# 467444_130_3_5-A.net
KiCad netlist of a schematic drawn in Altium Designer
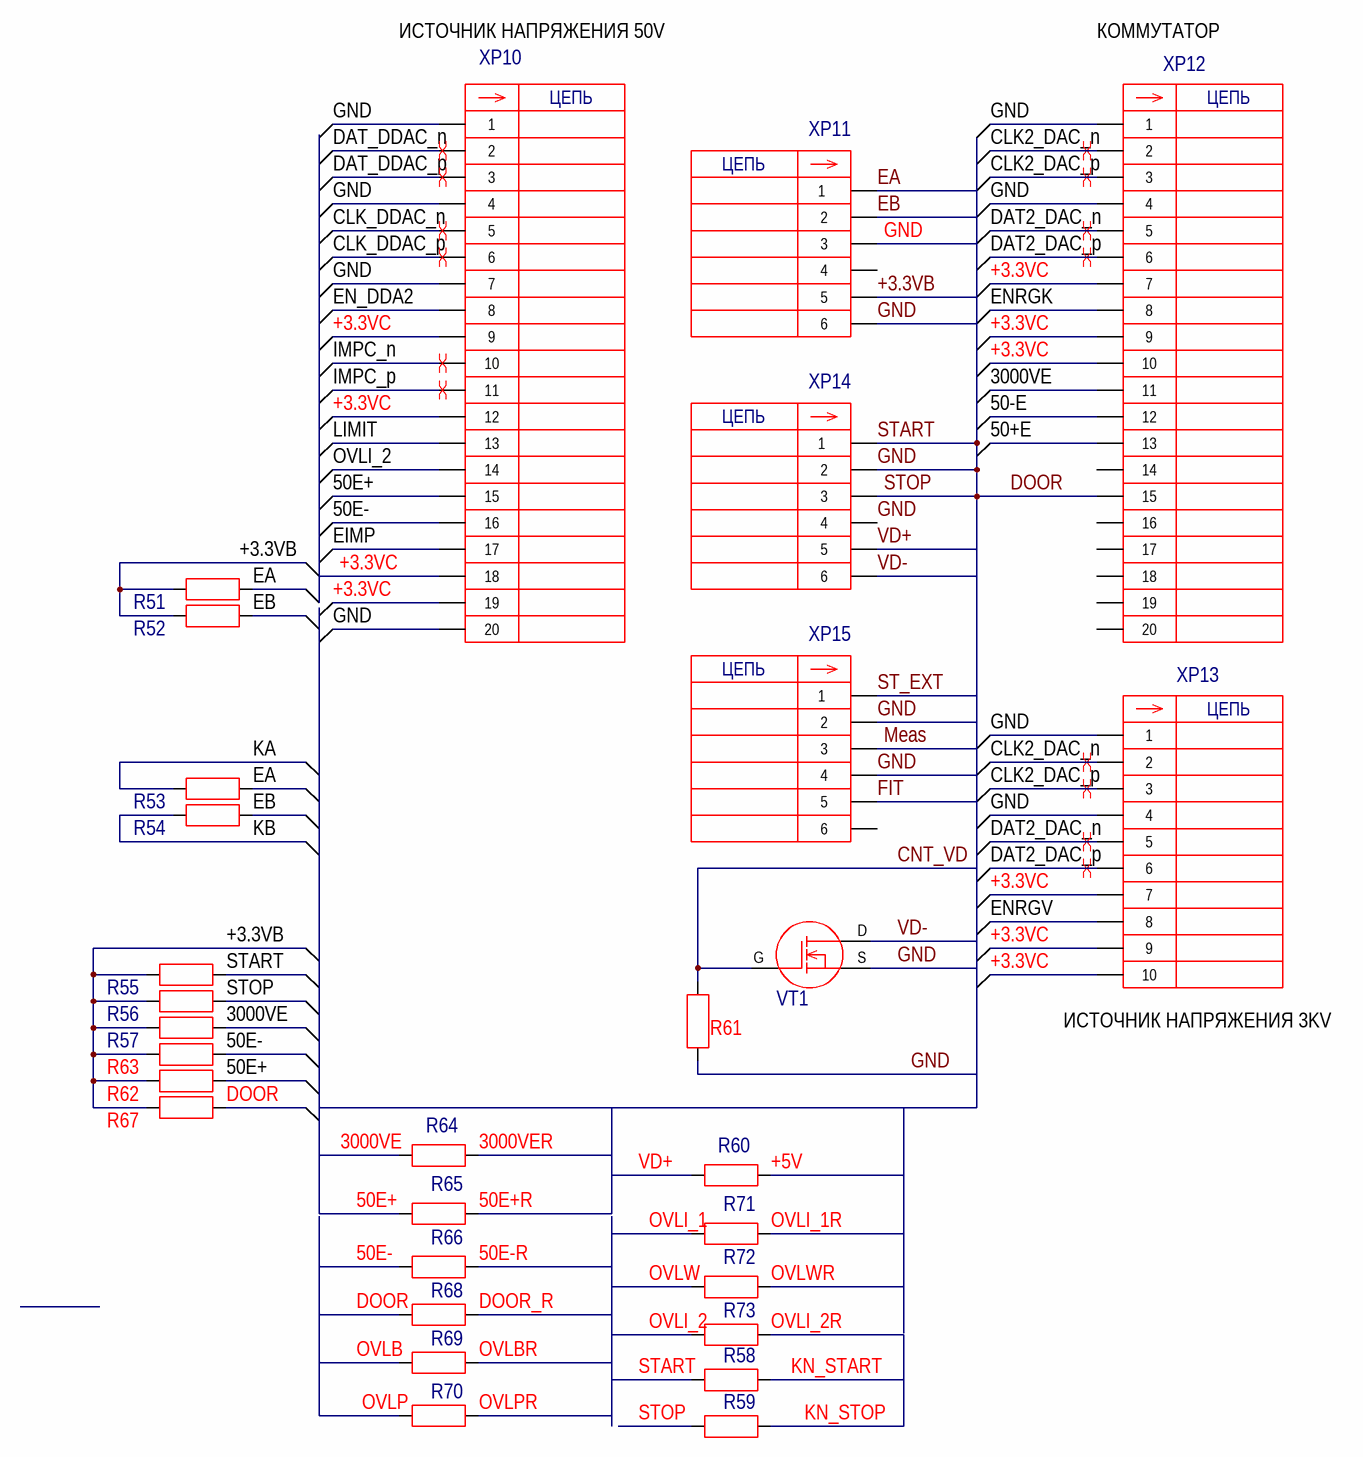
[diagram p0: УШЯИ.467444.130Э3_5-A.SchDoc]

(export (version "E")
  (design (tool "Eeschema 10.0.6"))
  (components
    (comp (ref "R51")
      (value "10k")
      (footprint "R_0805 [2012 Metric]")
      (fields (field (name "TOLERANCE") "±1%"))
      (libsource (lib "lib") (part "R_Const"))
    )
    (comp (ref "R52")
      (value "10k")
      (footprint "R_0805 [2012 Metric]")
      (fields (field (name "TOLERANCE") "±1%"))
      (libsource (lib "lib") (part "R_Const"))
    )
    (comp (ref "R53")
      (value "10k")
      (footprint "R_0805 [2012 Metric]")
      (fields (field (name "TOLERANCE") "±1%"))
      (libsource (lib "lib") (part "R_Const"))
    )
    (comp (ref "R54")
      (value "10k")
      (footprint "R_0805 [2012 Metric]")
      (fields (field (name "TOLERANCE") "±1%"))
      (libsource (lib "lib") (part "R_Const"))
    )
    (comp (ref "R55")
      (value "10k")
      (footprint "R_0805 [2012 Metric]")
      (fields (field (name "TOLERANCE") "±1%"))
      (libsource (lib "lib") (part "R_Const"))
    )
    (comp (ref "R56")
      (value "10k")
      (footprint "R_0805 [2012 Metric]")
      (fields (field (name "TOLERANCE") "±1%"))
      (libsource (lib "lib") (part "R_Const"))
    )
    (comp (ref "R57")
      (value "10k")
      (footprint "R_0805 [2012 Metric]")
      (fields (field (name "TOLERANCE") "±1%"))
      (libsource (lib "lib") (part "R_Const"))
    )
    (comp (ref "R58")
      (value "10k")
      (footprint "R_0805 [2012 Metric]")
      (fields (field (name "TOLERANCE") "±1%"))
      (libsource (lib "lib") (part "R_Const"))
    )
    (comp (ref "R59")
      (value "10k")
      (footprint "R_0805 [2012 Metric]")
      (fields (field (name "TOLERANCE") "±1%"))
      (libsource (lib "lib") (part "R_Const"))
    )
    (comp (ref "R60")
      (value "10k")
      (footprint "R_0805 [2012 Metric]")
      (fields (field (name "TOLERANCE") "±1%"))
      (libsource (lib "lib") (part "R_Const"))
    )
    (comp (ref "R61")
      (value "10k")
      (footprint "R_1206 [3216 Metric]")
      (fields (field (name "TOLERANCE") "±5%"))
      (libsource (lib "Lib_MN") (part "R_Const"))
    )
    (comp (ref "R62")
      (value "10k")
      (footprint "R_0805 [2012 Metric]")
      (fields (field (name "TOLERANCE") "±1%"))
      (libsource (lib "lib") (part "R_Const"))
    )
    (comp (ref "R63")
      (value "10k")
      (footprint "R_0805 [2012 Metric]")
      (fields (field (name "TOLERANCE") "±1%"))
      (libsource (lib "lib") (part "R_Const"))
    )
    (comp (ref "R64")
      (value "10k")
      (footprint "R_0805 [2012 Metric]")
      (fields (field (name "TOLERANCE") "±1%"))
      (libsource (lib "lib") (part "R_Const"))
    )
    (comp (ref "R65")
      (value "10k")
      (footprint "R_0805 [2012 Metric]")
      (fields (field (name "TOLERANCE") "±1%"))
      (libsource (lib "lib") (part "R_Const"))
    )
    (comp (ref "R66")
      (value "10k")
      (footprint "R_0805 [2012 Metric]")
      (fields (field (name "TOLERANCE") "±1%"))
      (libsource (lib "lib") (part "R_Const"))
    )
    (comp (ref "R67")
      (value "10k")
      (footprint "R_0805 [2012 Metric]")
      (fields (field (name "TOLERANCE") "±1%"))
      (libsource (lib "lib") (part "R_Const"))
    )
    (comp (ref "R68")
      (value "10k")
      (footprint "R_0805 [2012 Metric]")
      (fields (field (name "TOLERANCE") "±1%"))
      (libsource (lib "lib") (part "R_Const"))
    )
    (comp (ref "R69")
      (value "10k")
      (footprint "R_0805 [2012 Metric]")
      (fields (field (name "TOLERANCE") "±1%"))
      (libsource (lib "lib") (part "R_Const"))
    )
    (comp (ref "R70")
      (value "10k")
      (footprint "R_0805 [2012 Metric]")
      (fields (field (name "TOLERANCE") "±1%"))
      (libsource (lib "lib") (part "R_Const"))
    )
    (comp (ref "R71")
      (value "10k")
      (footprint "R_0805 [2012 Metric]")
      (fields (field (name "TOLERANCE") "±1%"))
      (libsource (lib "lib") (part "R_Const"))
    )
    (comp (ref "R72")
      (value "10k")
      (footprint "R_0805 [2012 Metric]")
      (fields (field (name "TOLERANCE") "±1%"))
      (libsource (lib "lib") (part "R_Const"))
    )
    (comp (ref "R73")
      (value "10k")
      (footprint "R_0805 [2012 Metric]")
      (fields (field (name "TOLERANCE") "±1%"))
      (libsource (lib "lib") (part "R_Const"))
    )
    (comp (ref "VT1")
      (value "NDS7002A")
      (footprint "SOT-23-3_[TO-236AB]_Transistor_n")
      (description "Транзистор n-канальный, изолированный затвор")
      (fields (field (name "MANUFACTURER") "Onsemi"))
      (libsource (lib "Lib_MN") (part "n-channel"))
    )
    (comp (ref "XP10")
      (value "BH2-20R")
      (footprint "BH2-20R")
      (description "Male, 20 pins, 2 rows, Right Angle, DS1014-20RF1B-B, 2 mm")
      (fields (field (name "MANUFACTURER") "Connfly electronic"))
      (libsource (lib "lib") (part "M_20"))
    )
    (comp (ref "XP11")
      (value "AMPMODU II 280372-2")
      (footprint "AMP II-280372-2")
      (description "Male, 6 pin, 1 row, Vertical, Board-to-Board, 2.54 mm")
      (fields (field (name "MANUFACTURER") "TE Connectivity"))
      (libsource (lib "Lib_MN") (part "M_6"))
    )
    (comp (ref "XP12")
      (value "BH2-20R")
      (footprint "BH2-20R")
      (description "Male, 20 pins, 2 rows, Right Angle, DS1014-20RF1B-B, 2 mm")
      (fields (field (name "MANUFACTURER") "Connfly electronic"))
      (libsource (lib "lib") (part "M_20"))
    )
    (comp (ref "XP13")
      (value "BH2-10R")
      (footprint "BH2-10R")
      (description "Male, 10 pins, 2 rows, Vertical, DS1014-10RF1B-B, 2 mm")
      (fields (field (name "MANUFACTURER") "Connfly electronic"))
      (libsource (lib "lib") (part "M_10"))
    )
    (comp (ref "XP14")
      (value "AMPMODU II 280372-2")
      (footprint "AMP II-280372-2")
      (description "Male, 6 pin, 1 row, Vertical, Board-to-Board, 2.54 mm")
      (fields (field (name "MANUFACTURER") "TE Connectivity"))
      (libsource (lib "Lib_MN") (part "M_6"))
    )
    (comp (ref "XP15")
      (value "AMPMODU II 280372-2")
      (footprint "AMP II-280372-2")
      (description "Male, 6 pin, 1 row, Vertical, Board-to-Board, 2.54 mm")
      (fields (field (name "MANUFACTURER") "TE Connectivity"))
      (libsource (lib "Lib_MN") (part "M_6"))
    )
  )
  (nets
    (net (code "1") (name "/+3.3VB") (class "Default")
      (node (ref "R51") (pin "1") (pinfunction "1_1") (pintype "passive"))
      (node (ref "R52") (pin "1") (pinfunction "1_1") (pintype "passive"))
      (node (ref "R55") (pin "1") (pinfunction "1_1") (pintype "passive"))
      (node (ref "R56") (pin "1") (pinfunction "1_1") (pintype "passive"))
      (node (ref "R57") (pin "1") (pinfunction "1_1") (pintype "passive"))
      (node (ref "R62") (pin "1") (pinfunction "1_1") (pintype "passive"))
      (node (ref "R63") (pin "1") (pinfunction "1_1") (pintype "passive"))
      (node (ref "R67") (pin "1") (pinfunction "1_1") (pintype "passive"))
      (node (ref "XP11") (pin "5") (pinfunction "5_5") (pintype "passive"))
    )
    (net (code "2") (name "/+3.3VC") (class "Default")
      (node (ref "XP10") (pin "12") (pinfunction "12_12") (pintype "passive"))
      (node (ref "XP10") (pin "18") (pinfunction "18_18") (pintype "passive"))
      (node (ref "XP10") (pin "19") (pinfunction "19_19") (pintype "passive"))
      (node (ref "XP10") (pin "9") (pinfunction "9_9") (pintype "passive"))
      (node (ref "XP12") (pin "10") (pinfunction "10_10") (pintype "passive"))
      (node (ref "XP12") (pin "7") (pinfunction "7_7") (pintype "passive"))
      (node (ref "XP12") (pin "9") (pinfunction "9_9") (pintype "passive"))
      (node (ref "XP13") (pin "10") (pinfunction "10_10") (pintype "passive"))
      (node (ref "XP13") (pin "7") (pinfunction "7_7") (pintype "passive"))
      (node (ref "XP13") (pin "9") (pinfunction "9_9") (pintype "passive"))
    )
    (net (code "3") (name "/+5V") (class "Default")
      (node (ref "R60") (pin "2") (pinfunction "2_2") (pintype "passive"))
    )
    (net (code "4") (name "/50+E") (class "Default")
      (node (ref "XP12") (pin "13") (pinfunction "13_13") (pintype "passive"))
    )
    (net (code "5") (name "/50-E") (class "Default")
      (node (ref "XP12") (pin "12") (pinfunction "12_12") (pintype "passive"))
    )
    (net (code "6") (name "/50E+") (class "Default")
      (node (ref "R62") (pin "2") (pinfunction "2_2") (pintype "passive"))
      (node (ref "R65") (pin "1") (pinfunction "1_1") (pintype "passive"))
      (node (ref "XP10") (pin "15") (pinfunction "15_15") (pintype "passive"))
    )
    (net (code "7") (name "/50E+R") (class "Default")
      (node (ref "R65") (pin "2") (pinfunction "2_2") (pintype "passive"))
    )
    (net (code "8") (name "/50E-") (class "Default")
      (node (ref "R63") (pin "2") (pinfunction "2_2") (pintype "passive"))
      (node (ref "R66") (pin "1") (pinfunction "1_1") (pintype "passive"))
      (node (ref "XP10") (pin "16") (pinfunction "16_16") (pintype "passive"))
    )
    (net (code "9") (name "/50E-R") (class "Default")
      (node (ref "R66") (pin "2") (pinfunction "2_2") (pintype "passive"))
    )
    (net (code "10") (name "/3000VE") (class "Default")
      (node (ref "R57") (pin "2") (pinfunction "2_2") (pintype "passive"))
      (node (ref "R64") (pin "1") (pinfunction "1_1") (pintype "passive"))
      (node (ref "XP12") (pin "11") (pinfunction "11_11") (pintype "passive"))
    )
    (net (code "11") (name "/3000VER") (class "Default")
      (node (ref "R64") (pin "2") (pinfunction "2_2") (pintype "passive"))
    )
    (net (code "12") (name "/CLK2_DAC_n") (class "Default")
      (node (ref "XP12") (pin "2") (pinfunction "2_2") (pintype "passive"))
      (node (ref "XP13") (pin "2") (pinfunction "2_2") (pintype "passive"))
    )
    (net (code "13") (name "/CLK2_DAC_p") (class "Default")
      (node (ref "XP12") (pin "3") (pinfunction "3_3") (pintype "passive"))
      (node (ref "XP13") (pin "3") (pinfunction "3_3") (pintype "passive"))
    )
    (net (code "14") (name "/CLK_DDAC_n") (class "Default")
      (node (ref "XP10") (pin "5") (pinfunction "5_5") (pintype "passive"))
    )
    (net (code "15") (name "/CLK_DDAC_p") (class "Default")
      (node (ref "XP10") (pin "6") (pinfunction "6_6") (pintype "passive"))
    )
    (net (code "16") (name "/CNT_VD") (class "Default")
      (node (ref "R61") (pin "2") (pinfunction "2_2") (pintype "passive"))
      (node (ref "VT1") (pin "G") (pinfunction "З_G") (pintype "passive"))
    )
    (net (code "17") (name "/DAT2_DAC_n") (class "Default")
      (node (ref "XP12") (pin "5") (pinfunction "5_5") (pintype "passive"))
      (node (ref "XP13") (pin "5") (pinfunction "5_5") (pintype "passive"))
    )
    (net (code "18") (name "/DAT2_DAC_p") (class "Default")
      (node (ref "XP12") (pin "6") (pinfunction "6_6") (pintype "passive"))
      (node (ref "XP13") (pin "6") (pinfunction "6_6") (pintype "passive"))
    )
    (net (code "19") (name "/DAT_DDAC_n") (class "Default")
      (node (ref "XP10") (pin "2") (pinfunction "2_2") (pintype "passive"))
    )
    (net (code "20") (name "/DAT_DDAC_p") (class "Default")
      (node (ref "XP10") (pin "3") (pinfunction "3_3") (pintype "passive"))
    )
    (net (code "21") (name "/DOOR") (class "Default")
      (node (ref "R55") (pin "2") (pinfunction "2_2") (pintype "passive"))
      (node (ref "R56") (pin "2") (pinfunction "2_2") (pintype "passive"))
      (node (ref "R58") (pin "1") (pinfunction "1_1") (pintype "passive"))
      (node (ref "R59") (pin "1") (pinfunction "1_1") (pintype "passive"))
      (node (ref "R61") (pin "1") (pinfunction "1_1") (pintype "passive"))
      (node (ref "R67") (pin "2") (pinfunction "2_2") (pintype "passive"))
      (node (ref "R68") (pin "1") (pinfunction "1_1") (pintype "passive"))
      (node (ref "VT1") (pin "S") (pinfunction "И_S") (pintype "passive"))
      (node (ref "XP10") (pin "1") (pinfunction "1_1") (pintype "passive"))
      (node (ref "XP10") (pin "20") (pinfunction "20_20") (pintype "passive"))
      (node (ref "XP10") (pin "4") (pinfunction "4_4") (pintype "passive"))
      (node (ref "XP10") (pin "7") (pinfunction "7_7") (pintype "passive"))
      (node (ref "XP11") (pin "3") (pinfunction "3_3") (pintype "passive"))
      (node (ref "XP11") (pin "6") (pinfunction "6_6") (pintype "passive"))
      (node (ref "XP12") (pin "1") (pinfunction "1_1") (pintype "passive"))
      (node (ref "XP12") (pin "15") (pinfunction "15_15") (pintype "passive"))
      (node (ref "XP12") (pin "4") (pinfunction "4_4") (pintype "passive"))
      (node (ref "XP13") (pin "1") (pinfunction "1_1") (pintype "passive"))
      (node (ref "XP13") (pin "4") (pinfunction "4_4") (pintype "passive"))
      (node (ref "XP14") (pin "1") (pinfunction "1_1") (pintype "passive"))
      (node (ref "XP14") (pin "2") (pinfunction "2_2") (pintype "passive"))
      (node (ref "XP14") (pin "3") (pinfunction "3_3") (pintype "passive"))
      (node (ref "XP14") (pin "4") (pinfunction "4_4") (pintype "passive"))
      (node (ref "XP15") (pin "2") (pinfunction "2_2") (pintype "passive"))
      (node (ref "XP15") (pin "4") (pinfunction "4_4") (pintype "passive"))
    )
    (net (code "22") (name "/DOOR_R") (class "Default")
      (node (ref "R68") (pin "2") (pinfunction "2_2") (pintype "passive"))
    )
    (net (code "23") (name "/EA") (class "Default")
      (node (ref "R51") (pin "2") (pinfunction "2_2") (pintype "passive"))
      (node (ref "R53") (pin "2") (pinfunction "2_2") (pintype "passive"))
      (node (ref "XP11") (pin "1") (pinfunction "1_1") (pintype "passive"))
    )
    (net (code "24") (name "/EB") (class "Default")
      (node (ref "R52") (pin "2") (pinfunction "2_2") (pintype "passive"))
      (node (ref "R54") (pin "2") (pinfunction "2_2") (pintype "passive"))
      (node (ref "XP11") (pin "2") (pinfunction "2_2") (pintype "passive"))
    )
    (net (code "25") (name "/EIMP") (class "Default")
      (node (ref "XP10") (pin "17") (pinfunction "17_17") (pintype "passive"))
    )
    (net (code "26") (name "/ENRGK") (class "Default")
      (node (ref "XP12") (pin "8") (pinfunction "8_8") (pintype "passive"))
    )
    (net (code "27") (name "/ENRGV") (class "Default")
      (node (ref "XP13") (pin "8") (pinfunction "8_8") (pintype "passive"))
    )
    (net (code "28") (name "/EN_DDA2") (class "Default")
      (node (ref "XP10") (pin "8") (pinfunction "8_8") (pintype "passive"))
    )
    (net (code "29") (name "/FIT") (class "Default")
      (node (ref "XP15") (pin "5") (pinfunction "5_5") (pintype "passive"))
    )
    (net (code "30") (name "/IMPC_n") (class "Default")
      (node (ref "XP10") (pin "10") (pinfunction "10_10") (pintype "passive"))
    )
    (net (code "31") (name "/IMPC_p") (class "Default")
      (node (ref "XP10") (pin "11") (pinfunction "11_11") (pintype "passive"))
    )
    (net (code "32") (name "/KA") (class "Default")
      (node (ref "R53") (pin "1") (pinfunction "1_1") (pintype "passive"))
    )
    (net (code "33") (name "/KB") (class "Default")
      (node (ref "R54") (pin "1") (pinfunction "1_1") (pintype "passive"))
    )
    (net (code "34") (name "/KN_START") (class "Default")
      (node (ref "R58") (pin "2") (pinfunction "2_2") (pintype "passive"))
    )
    (net (code "35") (name "/KN_STOP") (class "Default")
      (node (ref "R59") (pin "2") (pinfunction "2_2") (pintype "passive"))
    )
    (net (code "36") (name "/LIMIT") (class "Default")
      (node (ref "XP10") (pin "13") (pinfunction "13_13") (pintype "passive"))
    )
    (net (code "37") (name "/Meas") (class "Default")
      (node (ref "XP15") (pin "3") (pinfunction "3_3") (pintype "passive"))
    )
    (net (code "38") (name "/OVLB") (class "Default")
      (node (ref "R69") (pin "1") (pinfunction "1_1") (pintype "passive"))
    )
    (net (code "39") (name "/OVLBR") (class "Default")
      (node (ref "R69") (pin "2") (pinfunction "2_2") (pintype "passive"))
    )
    (net (code "40") (name "/OVLI_1") (class "Default")
      (node (ref "R71") (pin "1") (pinfunction "1_1") (pintype "passive"))
    )
    (net (code "41") (name "/OVLI_1R") (class "Default")
      (node (ref "R71") (pin "2") (pinfunction "2_2") (pintype "passive"))
    )
    (net (code "42") (name "/OVLI_2") (class "Default")
      (node (ref "R73") (pin "1") (pinfunction "1_1") (pintype "passive"))
      (node (ref "XP10") (pin "14") (pinfunction "14_14") (pintype "passive"))
    )
    (net (code "43") (name "/OVLI_2R") (class "Default")
      (node (ref "R73") (pin "2") (pinfunction "2_2") (pintype "passive"))
    )
    (net (code "44") (name "/OVLP") (class "Default")
      (node (ref "R70") (pin "1") (pinfunction "1_1") (pintype "passive"))
    )
    (net (code "45") (name "/OVLPR") (class "Default")
      (node (ref "R70") (pin "2") (pinfunction "2_2") (pintype "passive"))
    )
    (net (code "46") (name "/OVLW") (class "Default")
      (node (ref "R72") (pin "1") (pinfunction "1_1") (pintype "passive"))
    )
    (net (code "47") (name "/OVLWR") (class "Default")
      (node (ref "R72") (pin "2") (pinfunction "2_2") (pintype "passive"))
    )
    (net (code "48") (name "/ST_EXT") (class "Default")
      (node (ref "XP15") (pin "1") (pinfunction "1_1") (pintype "passive"))
    )
    (net (code "49") (name "/VD+") (class "Default")
      (node (ref "R60") (pin "1") (pinfunction "1_1") (pintype "passive"))
      (node (ref "XP14") (pin "5") (pinfunction "5_5") (pintype "passive"))
    )
    (net (code "50") (name "/VD-") (class "Default")
      (node (ref "VT1") (pin "D") (pinfunction "C_D") (pintype "passive"))
      (node (ref "XP14") (pin "6") (pinfunction "6_6") (pintype "passive"))
    )
    (net (code "51") (name "unconnected-(XP11-Pad4)") (class "Default")
      (node (ref "XP11") (pin "4") (pinfunction "4_4") (pintype "passive"))
    )
    (net (code "52") (name "unconnected-(XP12-Pad14)") (class "Default")
      (node (ref "XP12") (pin "14") (pinfunction "14_14") (pintype "passive"))
    )
    (net (code "53") (name "unconnected-(XP12-Pad16)") (class "Default")
      (node (ref "XP12") (pin "16") (pinfunction "16_16") (pintype "passive"))
    )
    (net (code "54") (name "unconnected-(XP12-Pad17)") (class "Default")
      (node (ref "XP12") (pin "17") (pinfunction "17_17") (pintype "passive"))
    )
    (net (code "55") (name "unconnected-(XP12-Pad18)") (class "Default")
      (node (ref "XP12") (pin "18") (pinfunction "18_18") (pintype "passive"))
    )
    (net (code "56") (name "unconnected-(XP12-Pad19)") (class "Default")
      (node (ref "XP12") (pin "19") (pinfunction "19_19") (pintype "passive"))
    )
    (net (code "57") (name "unconnected-(XP12-Pad20)") (class "Default")
      (node (ref "XP12") (pin "20") (pinfunction "20_20") (pintype "passive"))
    )
    (net (code "58") (name "unconnected-(XP15-Pad6)") (class "Default")
      (node (ref "XP15") (pin "6") (pinfunction "6_6") (pintype "passive"))
    )
  )
)
